# ground_station_power_board.net
KiCad netlist of a schematic drawn in EAGLE
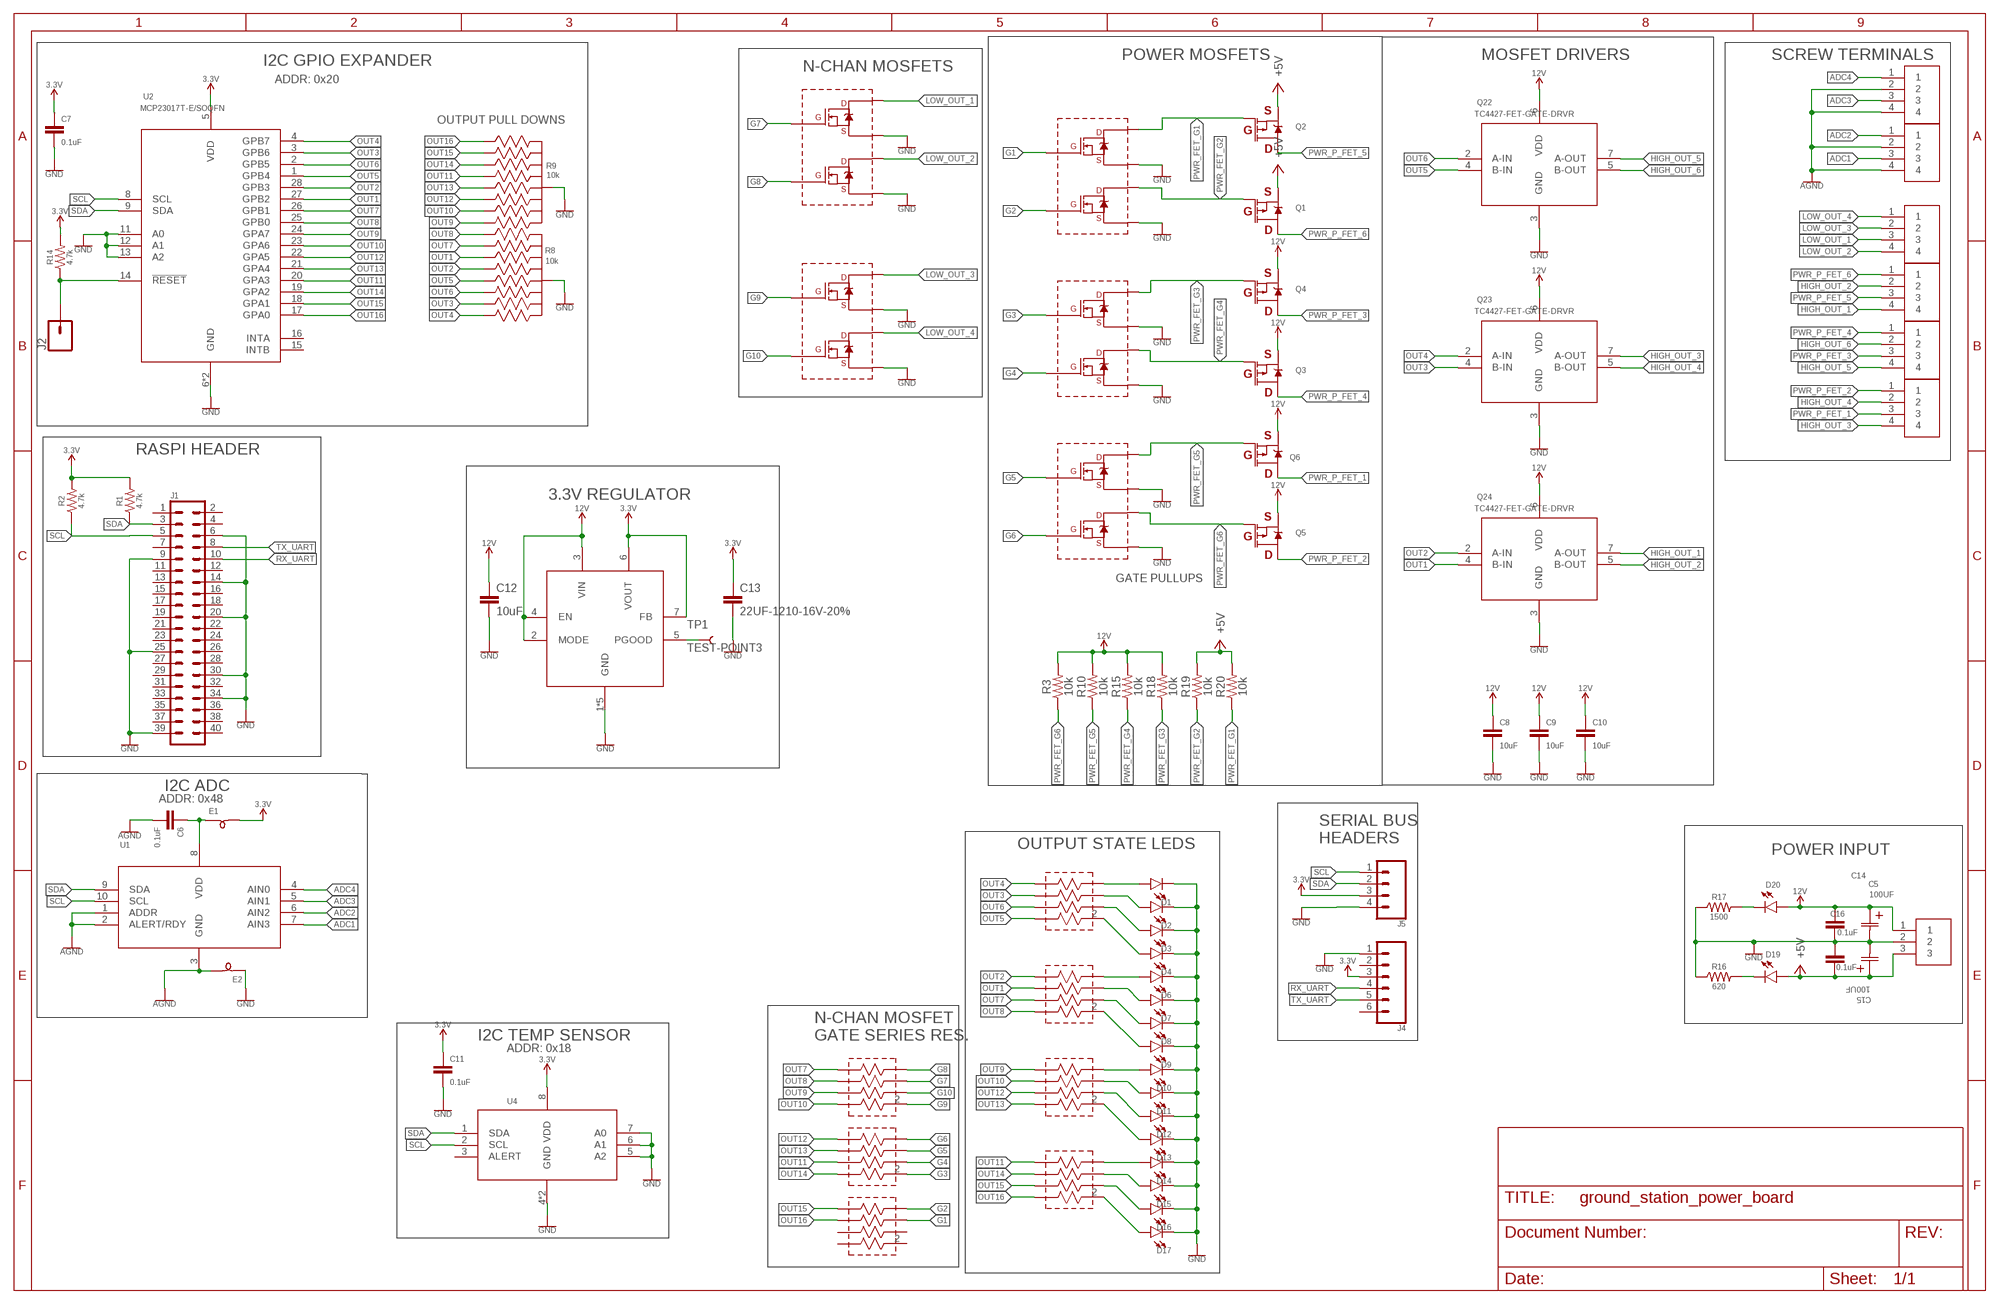
[diagram p0: schematic, sheet 1]

(export (version "E")
  (design (tool "Eeschema 10.0.6"))
  (components
    (comp (ref "C5")
      (value "100UF")
      (footprint "eagle-import:CHEMI-KE0-M")
      (fields (field (name "MANUFACTURER_PART_NUMBER") "EMVH630ARA101MKE0S"))
      (libsource (lib "eagle-import") (part "100UF-CAP-EMVH630ARA101MKE0SCHEMI-KE0-M"))
    )
    (comp (ref "C6")
      (value "0.1uF")
      (footprint "eagle-import:0603")
      (libsource (lib "eagle-import") (part "0.1UF-0603-25V-5%"))
    )
    (comp (ref "C7")
      (value "0.1uF")
      (footprint "eagle-import:0603")
      (libsource (lib "eagle-import") (part "0.1UF-0603-25V-5%"))
    )
    (comp (ref "C8")
      (value "10uF")
      (footprint "eagle-import:0805")
      (libsource (lib "eagle-import") (part "10UF-0805-10V-10%"))
    )
    (comp (ref "C9")
      (value "10uF")
      (footprint "eagle-import:0805")
      (libsource (lib "eagle-import") (part "10UF-0805-10V-10%"))
    )
    (comp (ref "C10")
      (value "10uF")
      (footprint "eagle-import:0805")
      (libsource (lib "eagle-import") (part "10UF-0805-10V-10%"))
    )
    (comp (ref "C11")
      (value "0.1uF")
      (footprint "eagle-import:0603")
      (libsource (lib "eagle-import") (part "0.1UF-0603-25V-5%"))
    )
    (comp (ref "C12")
      (value "10uF")
      (footprint "eagle-import:1206")
      (libsource (lib "eagle-import") (part "10UF-1206-6.3V-20%"))
    )
    (comp (ref "C13")
      (value "22UF-1210-16V-20%")
      (footprint "eagle-import:1210")
      (libsource (lib "eagle-import") (part "22UF-1210-16V-20%"))
    )
    (comp (ref "C14")
      (value "0.1uF")
      (footprint "eagle-import:0603")
      (libsource (lib "eagle-import") (part "0.1UF-0603-25V-5%"))
    )
    (comp (ref "C15")
      (value "100UF")
      (footprint "eagle-import:CHEMI-KE0-M")
      (fields (field (name "MANUFACTURER_PART_NUMBER") "EMVH630ARA101MKE0S"))
      (libsource (lib "eagle-import") (part "100UF-CAP-EMVH630ARA101MKE0SCHEMI-KE0-M"))
    )
    (comp (ref "C16")
      (value "0.1uF")
      (footprint "eagle-import:0603")
      (libsource (lib "eagle-import") (part "0.1UF-0603-25V-5%"))
    )
    (comp (ref "D1")
      (value "LED0603")
      (footprint "eagle-import:LED-0603")
      (libsource (lib "eagle-import") (part "LED0603"))
    )
    (comp (ref "D2")
      (value "LED0603")
      (footprint "eagle-import:LED-0603")
      (libsource (lib "eagle-import") (part "LED0603"))
    )
    (comp (ref "D3")
      (value "LED0603")
      (footprint "eagle-import:LED-0603")
      (libsource (lib "eagle-import") (part "LED0603"))
    )
    (comp (ref "D4")
      (value "LED0603")
      (footprint "eagle-import:LED-0603")
      (libsource (lib "eagle-import") (part "LED0603"))
    )
    (comp (ref "D6")
      (value "LED0603")
      (footprint "eagle-import:LED-0603")
      (libsource (lib "eagle-import") (part "LED0603"))
    )
    (comp (ref "D7")
      (value "LED0603")
      (footprint "eagle-import:LED-0603")
      (libsource (lib "eagle-import") (part "LED0603"))
    )
    (comp (ref "D8")
      (value "LED0603")
      (footprint "eagle-import:LED-0603")
      (libsource (lib "eagle-import") (part "LED0603"))
    )
    (comp (ref "D9")
      (value "LED0603")
      (footprint "eagle-import:LED-0603")
      (libsource (lib "eagle-import") (part "LED0603"))
    )
    (comp (ref "D10")
      (value "LED0603")
      (footprint "eagle-import:LED-0603")
      (libsource (lib "eagle-import") (part "LED0603"))
    )
    (comp (ref "D11")
      (value "LED0603")
      (footprint "eagle-import:LED-0603")
      (libsource (lib "eagle-import") (part "LED0603"))
    )
    (comp (ref "D12")
      (value "LED0603")
      (footprint "eagle-import:LED-0603")
      (libsource (lib "eagle-import") (part "LED0603"))
    )
    (comp (ref "D13")
      (value "LED0603")
      (footprint "eagle-import:LED-0603")
      (libsource (lib "eagle-import") (part "LED0603"))
    )
    (comp (ref "D14")
      (value "LED0603")
      (footprint "eagle-import:LED-0603")
      (libsource (lib "eagle-import") (part "LED0603"))
    )
    (comp (ref "D15")
      (value "LED0603")
      (footprint "eagle-import:LED-0603")
      (libsource (lib "eagle-import") (part "LED0603"))
    )
    (comp (ref "D16")
      (value "LED0603")
      (footprint "eagle-import:LED-0603")
      (libsource (lib "eagle-import") (part "LED0603"))
    )
    (comp (ref "D17")
      (value "LED0603")
      (footprint "eagle-import:LED-0603")
      (libsource (lib "eagle-import") (part "LED0603"))
    )
    (comp (ref "D19")
      (value "LED0603")
      (footprint "eagle-import:LED-0603")
      (libsource (lib "eagle-import") (part "LED0603"))
    )
    (comp (ref "D20")
      (value "LED0603")
      (footprint "eagle-import:LED-0603")
      (libsource (lib "eagle-import") (part "LED0603"))
    )
    (comp (ref "E1")
      (value "L-BEAD-0805-B")
      (footprint "eagle-import:.0805-B")
      (libsource (lib "eagle-import") (part "L-BEAD-0805-B"))
    )
    (comp (ref "E2")
      (value "L-BEAD-0805-B")
      (footprint "eagle-import:.0805-B")
      (libsource (lib "eagle-import") (part "L-BEAD-0805-B"))
    )
    (comp (ref "J1")
      (value "CONN_20X2SHROUDED")
      (footprint "eagle-import:2X20_SHROUDED")
      (libsource (lib "eagle-import") (part "CONN_20X2SHROUDED"))
    )
    (comp (ref "J2")
      (value "CONN_01PTH_NO_SILK_KIT")
      (footprint "eagle-import:1X01NS_KIT")
      (libsource (lib "eagle-import") (part "CONN_01PTH_NO_SILK_KIT"))
    )
    (comp (ref "J4")
      (value "CONN_06LONGPADS")
      (footprint "eagle-import:1X06_LONGPADS")
      (libsource (lib "eagle-import") (part "CONN_06LONGPADS"))
    )
    (comp (ref "J5")
      (value "CONN_04LONGPADS")
      (footprint "eagle-import:1X04_LONGPADS")
      (libsource (lib "eagle-import") (part "CONN_04LONGPADS"))
    )
    (comp (ref "Q1")
      (value "SQJ459EP_MOSFET_P_CHAN")
      (footprint "eagle-import:POWERPAK_S0-8L")
      (libsource (lib "eagle-import") (part "SQJ459EP_MOSFET_P_CHAN"))
    )
    (comp (ref "Q2")
      (value "SQJ459EP_MOSFET_P_CHAN")
      (footprint "eagle-import:POWERPAK_S0-8L")
      (libsource (lib "eagle-import") (part "SQJ459EP_MOSFET_P_CHAN"))
    )
    (comp (ref "Q3")
      (value "SQJ459EP_MOSFET_P_CHAN")
      (footprint "eagle-import:POWERPAK_S0-8L")
      (libsource (lib "eagle-import") (part "SQJ459EP_MOSFET_P_CHAN"))
    )
    (comp (ref "Q4")
      (value "SQJ459EP_MOSFET_P_CHAN")
      (footprint "eagle-import:POWERPAK_S0-8L")
      (libsource (lib "eagle-import") (part "SQJ459EP_MOSFET_P_CHAN"))
    )
    (comp (ref "Q5")
      (value "SQJ459EP_MOSFET_P_CHAN")
      (footprint "eagle-import:POWERPAK_S0-8L")
      (libsource (lib "eagle-import") (part "SQJ459EP_MOSFET_P_CHAN"))
    )
    (comp (ref "Q6")
      (value "SQJ459EP_MOSFET_P_CHAN")
      (footprint "eagle-import:POWERPAK_S0-8L")
      (libsource (lib "eagle-import") (part "SQJ459EP_MOSFET_P_CHAN"))
    )
    (comp (ref "Q8")
      (value "DMN61D8LVT-DUAL-N-CHANNEL-MOSFET")
      (footprint "eagle-import:TSOT26")
      (libsource (lib "eagle-import") (part "DMN61D8LVT-DUAL-N-CHANNEL-MOSFET"))
    )
    (comp (ref "Q9")
      (value "DMN61D8LVT-DUAL-N-CHANNEL-MOSFET")
      (footprint "eagle-import:TSOT26")
      (libsource (lib "eagle-import") (part "DMN61D8LVT-DUAL-N-CHANNEL-MOSFET"))
    )
    (comp (ref "Q15")
      (value "DMN61D8LVT-DUAL-N-CHANNEL-MOSFET")
      (footprint "eagle-import:TSOT26")
      (libsource (lib "eagle-import") (part "DMN61D8LVT-DUAL-N-CHANNEL-MOSFET"))
    )
    (comp (ref "Q17")
      (value "DMN61D8LVT-DUAL-N-CHANNEL-MOSFET")
      (footprint "eagle-import:TSOT26")
      (libsource (lib "eagle-import") (part "DMN61D8LVT-DUAL-N-CHANNEL-MOSFET"))
    )
    (comp (ref "Q18")
      (value "DMN61D8LVT-DUAL-N-CHANNEL-MOSFET")
      (footprint "eagle-import:TSOT26")
      (libsource (lib "eagle-import") (part "DMN61D8LVT-DUAL-N-CHANNEL-MOSFET"))
    )
    (comp (ref "Q22")
      (value "TC4427-FET-GATE-DRVR")
      (footprint "eagle-import:TSSOP-8")
      (libsource (lib "eagle-import") (part "TC4427-FET-GATE-DRVR"))
    )
    (comp (ref "Q23")
      (value "TC4427-FET-GATE-DRVR")
      (footprint "eagle-import:TSSOP-8")
      (libsource (lib "eagle-import") (part "TC4427-FET-GATE-DRVR"))
    )
    (comp (ref "Q24")
      (value "TC4427-FET-GATE-DRVR")
      (footprint "eagle-import:TSSOP-8")
      (libsource (lib "eagle-import") (part "TC4427-FET-GATE-DRVR"))
    )
    (comp (ref "R1")
      (value "4.7k")
      (footprint "eagle-import:0603")
      (libsource (lib "eagle-import") (part "4.7KOHM-0603-1/10W-1%"))
    )
    (comp (ref "R2")
      (value "4.7k")
      (footprint "eagle-import:0603")
      (libsource (lib "eagle-import") (part "4.7KOHM-0603-1/10W-1%"))
    )
    (comp (ref "R3")
      (value "10k")
      (footprint "eagle-import:0603")
      (libsource (lib "eagle-import") (part "10KOHM-0603-1/10W-1%"))
    )
    (comp (ref "R4")
      (value "680")
      (footprint "eagle-import:RES-ARRAY-742C083")
      (libsource (lib "eagle-import") (part "RES-ARRAY-742C083"))
    )
    (comp (ref "R5")
      (value "680")
      (footprint "eagle-import:RES-ARRAY-742C083")
      (libsource (lib "eagle-import") (part "RES-ARRAY-742C083"))
    )
    (comp (ref "R6")
      (value "680")
      (footprint "eagle-import:RES-ARRAY-742C083")
      (libsource (lib "eagle-import") (part "RES-ARRAY-742C083"))
    )
    (comp (ref "R7")
      (value "680")
      (footprint "eagle-import:RES-ARRAY-742C083")
      (libsource (lib "eagle-import") (part "RES-ARRAY-742C083"))
    )
    (comp (ref "R8")
      (value "10k")
      (footprint "eagle-import:C_ARRAY_EXBA-M")
      (fields (field (name "MANUFACTURER_PART_NUMBER") "EXBA10P391J"))
      (libsource (lib "eagle-import") (part "EXB-A10P391JC_ARRAY_EXBA-M"))
    )
    (comp (ref "R9")
      (value "10k")
      (footprint "eagle-import:C_ARRAY_EXBA-M")
      (fields (field (name "MANUFACTURER_PART_NUMBER") "EXBA10P391J"))
      (libsource (lib "eagle-import") (part "EXB-A10P391JC_ARRAY_EXBA-M"))
    )
    (comp (ref "R10")
      (value "10k")
      (footprint "eagle-import:0603")
      (libsource (lib "eagle-import") (part "10KOHM-0603-1/10W-1%"))
    )
    (comp (ref "R11")
      (value "220")
      (footprint "eagle-import:RES-ARRAY-742C083")
      (libsource (lib "eagle-import") (part "RES-ARRAY-742C083"))
    )
    (comp (ref "R12")
      (value "220")
      (footprint "eagle-import:RES-ARRAY-742C083")
      (libsource (lib "eagle-import") (part "RES-ARRAY-742C083"))
    )
    (comp (ref "R13")
      (value "220")
      (footprint "eagle-import:RES-ARRAY-742C083")
      (libsource (lib "eagle-import") (part "RES-ARRAY-742C083"))
    )
    (comp (ref "R14")
      (value "4.7k")
      (footprint "eagle-import:0603")
      (libsource (lib "eagle-import") (part "4.7KOHM-0603-1/10W-1%"))
    )
    (comp (ref "R15")
      (value "10k")
      (footprint "eagle-import:0603")
      (libsource (lib "eagle-import") (part "10KOHM-0603-1/10W-1%"))
    )
    (comp (ref "R16")
      (value "620")
      (footprint "eagle-import:0603")
      (libsource (lib "eagle-import") (part "4.7KOHM-0603-1/10W-1%"))
    )
    (comp (ref "R17")
      (value "1500")
      (footprint "eagle-import:0603")
      (libsource (lib "eagle-import") (part "4.7KOHM-0603-1/10W-1%"))
    )
    (comp (ref "R18")
      (value "10k")
      (footprint "eagle-import:0603")
      (libsource (lib "eagle-import") (part "10KOHM-0603-1/10W-1%"))
    )
    (comp (ref "R19")
      (value "10k")
      (footprint "eagle-import:0603")
      (libsource (lib "eagle-import") (part "10KOHM-0603-1/10W-1%"))
    )
    (comp (ref "R20")
      (value "10k")
      (footprint "eagle-import:0603")
      (libsource (lib "eagle-import") (part "10KOHM-0603-1/10W-1%"))
    )
    (comp (ref "TP1")
      (value "TEST-POINT3")
      (footprint "eagle-import:PAD.03X.03")
      (libsource (lib "eagle-import") (part "TEST-POINT3"))
    )
    (comp (ref "U$1")
      (value "1719031-PHONEIX-CONTACT-DBL-TERMINAL-BLOCK")
      (footprint "eagle-import:1719031-PHONEIX-CONTACT-DBL-TERMINAL-BLOCK")
      (libsource (lib "eagle-import") (part "1719031-PHONEIX-CONTACT-DBL-TERMINAL-BLOCK"))
    )
    (comp (ref "U$2")
      (value "1719031-PHONEIX-CONTACT-DBL-TERMINAL-BLOCK")
      (footprint "eagle-import:1719031-PHONEIX-CONTACT-DBL-TERMINAL-BLOCK")
      (libsource (lib "eagle-import") (part "1719031-PHONEIX-CONTACT-DBL-TERMINAL-BLOCK"))
    )
    (comp (ref "U$3")
      (value "1719031-PHONEIX-CONTACT-DBL-TERMINAL-BLOCK")
      (footprint "eagle-import:1719031-PHONEIX-CONTACT-DBL-TERMINAL-BLOCK")
      (libsource (lib "eagle-import") (part "1719031-PHONEIX-CONTACT-DBL-TERMINAL-BLOCK"))
    )
    (comp (ref "U$4")
      (value "1719031-PHONEIX-CONTACT-DBL-TERMINAL-BLOCK")
      (footprint "eagle-import:1719031-PHONEIX-CONTACT-DBL-TERMINAL-BLOCK")
      (libsource (lib "eagle-import") (part "1719031-PHONEIX-CONTACT-DBL-TERMINAL-BLOCK"))
    )
    (comp (ref "U$5")
      (value "1719031-PHONEIX-CONTACT-DBL-TERMINAL-BLOCK")
      (footprint "eagle-import:1719031-PHONEIX-CONTACT-DBL-TERMINAL-BLOCK")
      (libsource (lib "eagle-import") (part "1719031-PHONEIX-CONTACT-DBL-TERMINAL-BLOCK"))
    )
    (comp (ref "U$6")
      (value "1719031-PHONEIX-CONTACT-DBL-TERMINAL-BLOCK")
      (footprint "eagle-import:1719031-PHONEIX-CONTACT-DBL-TERMINAL-BLOCK")
      (libsource (lib "eagle-import") (part "1719031-PHONEIX-CONTACT-DBL-TERMINAL-BLOCK"))
    )
    (comp (ref "U$9")
      (value "LMZM23601V3SILT")
      (footprint "eagle-import:MICRO-SIP")
      (libsource (lib "eagle-import") (part "LMZM23601V3SILT"))
    )
    (comp (ref "U$11")
      (value "1714968-PHONEIX-CONTACT-TERMINAL-BLOCK")
      (footprint "eagle-import:1714968-PHONEIX-CONTACT-3-TERMINAL-BLOCK")
      (libsource (lib "eagle-import") (part "1714968-PHONEIX-CONTACT-TERMINAL-BLOCK"))
    )
    (comp (ref "U1")
      (value "ADS1115IDGSTDGS10-M")
      (footprint "eagle-import:DGS10-M")
      (fields (field (name "MANUFACTURER_PART_NUMBER") "ADS1115IDGST"))
      (libsource (lib "eagle-import") (part "ADS1115IDGSTDGS10-M"))
    )
    (comp (ref "U2")
      (value "MCP23017T-E/SOQFN")
      (footprint "eagle-import:QFN28_6X6MC-M")
      (libsource (lib "eagle-import") (part "MCP23017T-E/SOQFN"))
    )
    (comp (ref "U4")
      (value "MCP9808T-E/MCDFN8_2X3MC-M")
      (footprint "eagle-import:DFN8_2X3MC-M")
      (fields (field (name "MANUFACTURER_PART_NUMBER") "MCP9808TEMC"))
      (libsource (lib "eagle-import") (part "MCP9808T-E/MCDFN8_2X3MC-M"))
    )
  )
  (nets
    (net (code "1") (name "+5V") (class "Default")
      (node (ref "C15") (pin "1") (pinfunction "11_1") (pintype "passive"))
      (node (ref "C16") (pin "2") (pinfunction "2_2") (pintype "passive"))
      (node (ref "D19") (pin "A") (pinfunction "A_A") (pintype "passive"))
      (node (ref "Q1") (pin "S1") (pinfunction "S_S1") (pintype "bidirectional"))
      (node (ref "Q1") (pin "S2") (pinfunction "S_S2") (pintype "bidirectional"))
      (node (ref "Q1") (pin "S3") (pinfunction "S_S3") (pintype "bidirectional"))
      (node (ref "Q2") (pin "S1") (pinfunction "S_S1") (pintype "bidirectional"))
      (node (ref "Q2") (pin "S2") (pinfunction "S_S2") (pintype "bidirectional"))
      (node (ref "Q2") (pin "S3") (pinfunction "S_S3") (pintype "bidirectional"))
      (node (ref "R19") (pin "2") (pinfunction "2_2") (pintype "passive"))
      (node (ref "R20") (pin "2") (pinfunction "2_2") (pintype "passive"))
      (node (ref "U$11") (pin "3") (pinfunction "3_3") (pintype "bidirectional"))
    )
    (net (code "2") (name "3.3V") (class "Default")
      (node (ref "C11") (pin "1") (pinfunction "1_1") (pintype "passive"))
      (node (ref "C13") (pin "1") (pinfunction "1_1") (pintype "passive"))
      (node (ref "C7") (pin "1") (pinfunction "1_1") (pintype "passive"))
      (node (ref "E1") (pin "2") (pinfunction "2_2") (pintype "passive"))
      (node (ref "J4") (pin "3") (pinfunction "3_3") (pintype "passive"))
      (node (ref "J5") (pin "3") (pinfunction "3_3") (pintype "passive"))
      (node (ref "R1") (pin "2") (pinfunction "2_2") (pintype "passive"))
      (node (ref "R14") (pin "2") (pinfunction "2_2") (pintype "passive"))
      (node (ref "R2") (pin "2") (pinfunction "2_2") (pintype "passive"))
      (node (ref "U$9") (pin "6") (pinfunction "VOUT_6") (pintype "bidirectional"))
      (node (ref "U$9") (pin "7") (pinfunction "FB_7") (pintype "bidirectional"))
      (node (ref "U2") (pin "5") (pinfunction "VDD_5") (pintype "passive"))
      (node (ref "U4") (pin "8") (pinfunction "VDD_8") (pintype "power_in"))
    )
    (net (code "3") (name "12V") (class "Default")
      (node (ref "C10") (pin "1") (pinfunction "1_1") (pintype "passive"))
      (node (ref "C12") (pin "1") (pinfunction "1_1") (pintype "passive"))
      (node (ref "C14") (pin "1") (pinfunction "1_1") (pintype "passive"))
      (node (ref "C5") (pin "1") (pinfunction "11_1") (pintype "passive"))
      (node (ref "C8") (pin "1") (pinfunction "1_1") (pintype "passive"))
      (node (ref "C9") (pin "1") (pinfunction "1_1") (pintype "passive"))
      (node (ref "D20") (pin "A") (pinfunction "A_A") (pintype "passive"))
      (node (ref "Q22") (pin "6") (pinfunction "VDD_6") (pintype "passive"))
      (node (ref "Q23") (pin "6") (pinfunction "VDD_6") (pintype "passive"))
      (node (ref "Q24") (pin "6") (pinfunction "VDD_6") (pintype "passive"))
      (node (ref "Q3") (pin "S1") (pinfunction "S_S1") (pintype "bidirectional"))
      (node (ref "Q3") (pin "S2") (pinfunction "S_S2") (pintype "bidirectional"))
      (node (ref "Q3") (pin "S3") (pinfunction "S_S3") (pintype "bidirectional"))
      (node (ref "Q4") (pin "S1") (pinfunction "S_S1") (pintype "bidirectional"))
      (node (ref "Q4") (pin "S2") (pinfunction "S_S2") (pintype "bidirectional"))
      (node (ref "Q4") (pin "S3") (pinfunction "S_S3") (pintype "bidirectional"))
      (node (ref "Q5") (pin "S1") (pinfunction "S_S1") (pintype "bidirectional"))
      (node (ref "Q5") (pin "S2") (pinfunction "S_S2") (pintype "bidirectional"))
      (node (ref "Q5") (pin "S3") (pinfunction "S_S3") (pintype "bidirectional"))
      (node (ref "Q6") (pin "S1") (pinfunction "S_S1") (pintype "bidirectional"))
      (node (ref "Q6") (pin "S2") (pinfunction "S_S2") (pintype "bidirectional"))
      (node (ref "Q6") (pin "S3") (pinfunction "S_S3") (pintype "bidirectional"))
      (node (ref "R10") (pin "2") (pinfunction "2_2") (pintype "passive"))
      (node (ref "R15") (pin "2") (pinfunction "2_2") (pintype "passive"))
      (node (ref "R18") (pin "2") (pinfunction "2_2") (pintype "passive"))
      (node (ref "R3") (pin "2") (pinfunction "2_2") (pintype "passive"))
      (node (ref "U$11") (pin "1") (pinfunction "1_1") (pintype "bidirectional"))
      (node (ref "U$9") (pin "2") (pinfunction "MODE_2") (pintype "bidirectional"))
      (node (ref "U$9") (pin "3") (pinfunction "VIN_3") (pintype "bidirectional"))
      (node (ref "U$9") (pin "4") (pinfunction "EN_4") (pintype "bidirectional"))
    )
    (net (code "4") (name "ADC1") (class "Default")
      (node (ref "U$5") (pin "3") (pinfunction "3_3") (pintype "bidirectional"))
      (node (ref "U1") (pin "7") (pinfunction "AIN3_7") (pintype "input"))
    )
    (net (code "5") (name "ADC2") (class "Default")
      (node (ref "U$5") (pin "1") (pinfunction "1_1") (pintype "bidirectional"))
      (node (ref "U1") (pin "6") (pinfunction "AIN2_6") (pintype "input"))
    )
    (net (code "6") (name "ADC3") (class "Default")
      (node (ref "U$6") (pin "3") (pinfunction "3_3") (pintype "bidirectional"))
      (node (ref "U1") (pin "5") (pinfunction "AIN1_5") (pintype "input"))
    )
    (net (code "7") (name "ADC4") (class "Default")
      (node (ref "U$6") (pin "1") (pinfunction "1_1") (pintype "bidirectional"))
      (node (ref "U1") (pin "4") (pinfunction "AIN0_4") (pintype "input"))
    )
    (net (code "8") (name "AGND") (class "Default")
      (node (ref "C6") (pin "2") (pinfunction "2_2") (pintype "passive"))
      (node (ref "E2") (pin "2") (pinfunction "2_2") (pintype "passive"))
      (node (ref "U$5") (pin "2") (pinfunction "2_2") (pintype "bidirectional"))
      (node (ref "U$5") (pin "4") (pinfunction "4_4") (pintype "bidirectional"))
      (node (ref "U$6") (pin "2") (pinfunction "2_2") (pintype "bidirectional"))
      (node (ref "U$6") (pin "4") (pinfunction "4_4") (pintype "bidirectional"))
      (node (ref "U1") (pin "1") (pinfunction "ADDR_1") (pintype "input"))
      (node (ref "U1") (pin "2") (pinfunction "ALERT/RDY_2") (pintype "output"))
      (node (ref "U1") (pin "3") (pinfunction "GND_3") (pintype "power_in"))
    )
    (net (code "9") (name "G1") (class "Default")
      (node (ref "Q8") (pin "5") (pinfunction "G2_5") (pintype "bidirectional"))
      (node (ref "R11") (pin "6") (pinfunction "~{1OE6}_6") (pintype "bidirectional"))
    )
    (net (code "10") (name "G2") (class "Default")
      (node (ref "Q8") (pin "2") (pinfunction "G1_2") (pintype "bidirectional"))
      (node (ref "R11") (pin "8") (pinfunction "~{1OE8}_8") (pintype "bidirectional"))
    )
    (net (code "11") (name "G3") (class "Default")
      (node (ref "Q9") (pin "5") (pinfunction "G2_5") (pintype "bidirectional"))
      (node (ref "R12") (pin "2") (pinfunction "~{1OE2}_2") (pintype "bidirectional"))
    )
    (net (code "12") (name "G4") (class "Default")
      (node (ref "Q9") (pin "2") (pinfunction "G1_2") (pintype "bidirectional"))
      (node (ref "R12") (pin "4") (pinfunction "~{1OE4}_4") (pintype "bidirectional"))
    )
    (net (code "13") (name "G5") (class "Default")
      (node (ref "Q15") (pin "5") (pinfunction "G2_5") (pintype "bidirectional"))
      (node (ref "R12") (pin "6") (pinfunction "~{1OE6}_6") (pintype "bidirectional"))
    )
    (net (code "14") (name "G6") (class "Default")
      (node (ref "Q15") (pin "2") (pinfunction "G1_2") (pintype "bidirectional"))
      (node (ref "R12") (pin "8") (pinfunction "~{1OE8}_8") (pintype "bidirectional"))
    )
    (net (code "15") (name "G7") (class "Default")
      (node (ref "Q18") (pin "5") (pinfunction "G2_5") (pintype "bidirectional"))
      (node (ref "R13") (pin "6") (pinfunction "~{1OE6}_6") (pintype "bidirectional"))
    )
    (net (code "16") (name "G8") (class "Default")
      (node (ref "Q18") (pin "2") (pinfunction "G1_2") (pintype "bidirectional"))
      (node (ref "R13") (pin "8") (pinfunction "~{1OE8}_8") (pintype "bidirectional"))
    )
    (net (code "17") (name "G9") (class "Default")
      (node (ref "Q17") (pin "5") (pinfunction "G2_5") (pintype "bidirectional"))
      (node (ref "R13") (pin "2") (pinfunction "~{1OE2}_2") (pintype "bidirectional"))
    )
    (net (code "18") (name "G10") (class "Default")
      (node (ref "Q17") (pin "2") (pinfunction "G1_2") (pintype "bidirectional"))
      (node (ref "R13") (pin "4") (pinfunction "~{1OE4}_4") (pintype "bidirectional"))
    )
    (net (code "19") (name "GND") (class "Default")
      (node (ref "C10") (pin "2") (pinfunction "2_2") (pintype "passive"))
      (node (ref "C11") (pin "2") (pinfunction "2_2") (pintype "passive"))
      (node (ref "C12") (pin "2") (pinfunction "2_2") (pintype "passive"))
      (node (ref "C13") (pin "2") (pinfunction "2_2") (pintype "passive"))
      (node (ref "C14") (pin "2") (pinfunction "2_2") (pintype "passive"))
      (node (ref "C15") (pin "2") (pinfunction "22_2") (pintype "passive"))
      (node (ref "C16") (pin "1") (pinfunction "1_1") (pintype "passive"))
      (node (ref "C5") (pin "2") (pinfunction "22_2") (pintype "passive"))
      (node (ref "C7") (pin "2") (pinfunction "2_2") (pintype "passive"))
      (node (ref "C8") (pin "2") (pinfunction "2_2") (pintype "passive"))
      (node (ref "C9") (pin "2") (pinfunction "2_2") (pintype "passive"))
      (node (ref "D1") (pin "C") (pinfunction "C_C") (pintype "passive"))
      (node (ref "D10") (pin "C") (pinfunction "C_C") (pintype "passive"))
      (node (ref "D11") (pin "C") (pinfunction "C_C") (pintype "passive"))
      (node (ref "D12") (pin "C") (pinfunction "C_C") (pintype "passive"))
      (node (ref "D13") (pin "C") (pinfunction "C_C") (pintype "passive"))
      (node (ref "D14") (pin "C") (pinfunction "C_C") (pintype "passive"))
      (node (ref "D15") (pin "C") (pinfunction "C_C") (pintype "passive"))
      (node (ref "D16") (pin "C") (pinfunction "C_C") (pintype "passive"))
      (node (ref "D17") (pin "C") (pinfunction "C_C") (pintype "passive"))
      (node (ref "D2") (pin "C") (pinfunction "C_C") (pintype "passive"))
      (node (ref "D3") (pin "C") (pinfunction "C_C") (pintype "passive"))
      (node (ref "D4") (pin "C") (pinfunction "C_C") (pintype "passive"))
      (node (ref "D6") (pin "C") (pinfunction "C_C") (pintype "passive"))
      (node (ref "D7") (pin "C") (pinfunction "C_C") (pintype "passive"))
      (node (ref "D8") (pin "C") (pinfunction "C_C") (pintype "passive"))
      (node (ref "D9") (pin "C") (pinfunction "C_C") (pintype "passive"))
      (node (ref "E2") (pin "1") (pinfunction "1_1") (pintype "passive"))
      (node (ref "J1") (pin "14") (pinfunction "14_14") (pintype "passive"))
      (node (ref "J1") (pin "20") (pinfunction "20_20") (pintype "passive"))
      (node (ref "J1") (pin "25") (pinfunction "25_25") (pintype "passive"))
      (node (ref "J1") (pin "30") (pinfunction "30_30") (pintype "passive"))
      (node (ref "J1") (pin "34") (pinfunction "34_34") (pintype "passive"))
      (node (ref "J1") (pin "39") (pinfunction "39_39") (pintype "passive"))
      (node (ref "J1") (pin "6") (pinfunction "6_6") (pintype "passive"))
      (node (ref "J1") (pin "9") (pinfunction "9_9") (pintype "passive"))
      (node (ref "J4") (pin "1") (pinfunction "1_1") (pintype "passive"))
      (node (ref "J5") (pin "4") (pinfunction "4_4") (pintype "passive"))
      (node (ref "Q15") (pin "1") (pinfunction "S1_1") (pintype "bidirectional"))
      (node (ref "Q15") (pin "4") (pinfunction "S2_4") (pintype "bidirectional"))
      (node (ref "Q17") (pin "1") (pinfunction "S1_1") (pintype "bidirectional"))
      (node (ref "Q17") (pin "4") (pinfunction "S2_4") (pintype "bidirectional"))
      (node (ref "Q18") (pin "1") (pinfunction "S1_1") (pintype "bidirectional"))
      (node (ref "Q18") (pin "4") (pinfunction "S2_4") (pintype "bidirectional"))
      (node (ref "Q22") (pin "3") (pinfunction "GND_3") (pintype "passive"))
      (node (ref "Q23") (pin "3") (pinfunction "GND_3") (pintype "passive"))
      (node (ref "Q24") (pin "3") (pinfunction "GND_3") (pintype "passive"))
      (node (ref "Q8") (pin "1") (pinfunction "S1_1") (pintype "bidirectional"))
      (node (ref "Q8") (pin "4") (pinfunction "S2_4") (pintype "bidirectional"))
      (node (ref "Q9") (pin "1") (pinfunction "S1_1") (pintype "bidirectional"))
      (node (ref "Q9") (pin "4") (pinfunction "S2_4") (pintype "bidirectional"))
      (node (ref "R16") (pin "1") (pinfunction "1_1") (pintype "passive"))
      (node (ref "R17") (pin "1") (pinfunction "1_1") (pintype "passive"))
      (node (ref "R8") (pin "10") (pinfunction "55_10") (pintype "passive"))
      (node (ref "R8") (pin "5") (pinfunction "55_5") (pintype "passive"))
      (node (ref "R9") (pin "10") (pinfunction "55_10") (pintype "passive"))
      (node (ref "R9") (pin "5") (pinfunction "55_5") (pintype "passive"))
      (node (ref "U$11") (pin "2") (pinfunction "2_2") (pintype "bidirectional"))
      (node (ref "U$9") (pin "1") (pinfunction "GND_1") (pintype "bidirectional"))
      (node (ref "U$9") (pin "TP") (pinfunction "GND_TP") (pintype "bidirectional"))
      (node (ref "U$9") (pin "V1") (pinfunction "GND_V1") (pintype "bidirectional"))
      (node (ref "U$9") (pin "V2") (pinfunction "GND_V2") (pintype "bidirectional"))
      (node (ref "U$9") (pin "V3") (pinfunction "GND_V3") (pintype "bidirectional"))
      (node (ref "U2") (pin "11") (pinfunction "A0_11") (pintype "passive"))
      (node (ref "U2") (pin "12") (pinfunction "A1_12") (pintype "passive"))
      (node (ref "U2") (pin "13") (pinfunction "A2_13") (pintype "passive"))
      (node (ref "U2") (pin "29") (pinfunction "GND_29") (pintype "passive"))
      (node (ref "U2") (pin "6") (pinfunction "GND_6") (pintype "passive"))
      (node (ref "U4") (pin "4") (pinfunction "GND_4") (pintype "power_in"))
      (node (ref "U4") (pin "5") (pinfunction "A2_5") (pintype "passive"))
      (node (ref "U4") (pin "6") (pinfunction "A1_6") (pintype "passive"))
      (node (ref "U4") (pin "7") (pinfunction "A0_7") (pintype "passive"))
      (node (ref "U4") (pin "9") (pinfunction "GND_9") (pintype "power_in"))
    )
    (net (code "20") (name "HIGH_OUT_1") (class "Default")
      (node (ref "Q24") (pin "7") (pinfunction "A-OUT_7") (pintype "passive"))
      (node (ref "U$3") (pin "4") (pinfunction "4_4") (pintype "bidirectional"))
    )
    (net (code "21") (name "HIGH_OUT_2") (class "Default")
      (node (ref "Q24") (pin "5") (pinfunction "B-OUT_5") (pintype "passive"))
      (node (ref "U$3") (pin "2") (pinfunction "2_2") (pintype "bidirectional"))
    )
    (net (code "22") (name "HIGH_OUT_3") (class "Default")
      (node (ref "Q23") (pin "7") (pinfunction "A-OUT_7") (pintype "passive"))
      (node (ref "U$1") (pin "4") (pinfunction "4_4") (pintype "bidirectional"))
    )
    (net (code "23") (name "HIGH_OUT_4") (class "Default")
      (node (ref "Q23") (pin "5") (pinfunction "B-OUT_5") (pintype "passive"))
      (node (ref "U$1") (pin "2") (pinfunction "2_2") (pintype "bidirectional"))
    )
    (net (code "24") (name "HIGH_OUT_5") (class "Default")
      (node (ref "Q22") (pin "7") (pinfunction "A-OUT_7") (pintype "passive"))
      (node (ref "U$2") (pin "4") (pinfunction "4_4") (pintype "bidirectional"))
    )
    (net (code "25") (name "HIGH_OUT_6") (class "Default")
      (node (ref "Q22") (pin "5") (pinfunction "B-OUT_5") (pintype "passive"))
      (node (ref "U$2") (pin "2") (pinfunction "2_2") (pintype "bidirectional"))
    )
    (net (code "26") (name "LOW_OUT_1") (class "Default")
      (node (ref "Q18") (pin "3") (pinfunction "D2_3") (pintype "bidirectional"))
      (node (ref "U$4") (pin "3") (pinfunction "3_3") (pintype "bidirectional"))
    )
    (net (code "27") (name "LOW_OUT_2") (class "Default")
      (node (ref "Q18") (pin "6") (pinfunction "D1_6") (pintype "bidirectional"))
      (node (ref "U$4") (pin "4") (pinfunction "4_4") (pintype "bidirectional"))
    )
    (net (code "28") (name "LOW_OUT_3") (class "Default")
      (node (ref "Q17") (pin "3") (pinfunction "D2_3") (pintype "bidirectional"))
      (node (ref "U$4") (pin "2") (pinfunction "2_2") (pintype "bidirectional"))
    )
    (net (code "29") (name "LOW_OUT_4") (class "Default")
      (node (ref "Q17") (pin "6") (pinfunction "D1_6") (pintype "bidirectional"))
      (node (ref "U$4") (pin "1") (pinfunction "1_1") (pintype "bidirectional"))
    )
    (net (code "30") (name "Net-(D19-PadC)") (class "Default")
      (node (ref "D19") (pin "C") (pinfunction "C_C") (pintype "passive"))
      (node (ref "R16") (pin "2") (pinfunction "2_2") (pintype "passive"))
    )
    (net (code "31") (name "Net-(D20-PadC)") (class "Default")
      (node (ref "D20") (pin "C") (pinfunction "C_C") (pintype "passive"))
      (node (ref "R17") (pin "2") (pinfunction "2_2") (pintype "passive"))
    )
    (net (code "32") (name "Net-(R4-~{1OE2})") (class "Default")
      (node (ref "D4") (pin "A") (pinfunction "A_A") (pintype "passive"))
      (node (ref "R4") (pin "2") (pinfunction "~{1OE2}_2") (pintype "bidirectional"))
    )
    (net (code "33") (name "Net-(R4-~{1OE4})") (class "Default")
      (node (ref "D3") (pin "A") (pinfunction "A_A") (pintype "passive"))
      (node (ref "R4") (pin "4") (pinfunction "~{1OE4}_4") (pintype "bidirectional"))
    )
    (net (code "34") (name "Net-(R4-~{1OE6})") (class "Default")
      (node (ref "D2") (pin "A") (pinfunction "A_A") (pintype "passive"))
      (node (ref "R4") (pin "6") (pinfunction "~{1OE6}_6") (pintype "bidirectional"))
    )
    (net (code "35") (name "Net-(R4-~{1OE8})") (class "Default")
      (node (ref "D1") (pin "A") (pinfunction "A_A") (pintype "passive"))
      (node (ref "R4") (pin "8") (pinfunction "~{1OE8}_8") (pintype "bidirectional"))
    )
    (net (code "36") (name "Net-(R5-~{1OE2})") (class "Default")
      (node (ref "D9") (pin "A") (pinfunction "A_A") (pintype "passive"))
      (node (ref "R5") (pin "2") (pinfunction "~{1OE2}_2") (pintype "bidirectional"))
    )
    (net (code "37") (name "Net-(R5-~{1OE4})") (class "Default")
      (node (ref "D8") (pin "A") (pinfunction "A_A") (pintype "passive"))
      (node (ref "R5") (pin "4") (pinfunction "~{1OE4}_4") (pintype "bidirectional"))
    )
    (net (code "38") (name "Net-(R5-~{1OE6})") (class "Default")
      (node (ref "D7") (pin "A") (pinfunction "A_A") (pintype "passive"))
      (node (ref "R5") (pin "6") (pinfunction "~{1OE6}_6") (pintype "bidirectional"))
    )
    (net (code "39") (name "Net-(R5-~{1OE8})") (class "Default")
      (node (ref "D6") (pin "A") (pinfunction "A_A") (pintype "passive"))
      (node (ref "R5") (pin "8") (pinfunction "~{1OE8}_8") (pintype "bidirectional"))
    )
    (net (code "40") (name "Net-(R6-~{1OE2})") (class "Default")
      (node (ref "D13") (pin "A") (pinfunction "A_A") (pintype "passive"))
      (node (ref "R6") (pin "2") (pinfunction "~{1OE2}_2") (pintype "bidirectional"))
    )
    (net (code "41") (name "Net-(R6-~{1OE4})") (class "Default")
      (node (ref "D12") (pin "A") (pinfunction "A_A") (pintype "passive"))
      (node (ref "R6") (pin "4") (pinfunction "~{1OE4}_4") (pintype "bidirectional"))
    )
    (net (code "42") (name "Net-(R6-~{1OE6})") (class "Default")
      (node (ref "D11") (pin "A") (pinfunction "A_A") (pintype "passive"))
      (node (ref "R6") (pin "6") (pinfunction "~{1OE6}_6") (pintype "bidirectional"))
    )
    (net (code "43") (name "Net-(R6-~{1OE8})") (class "Default")
      (node (ref "D10") (pin "A") (pinfunction "A_A") (pintype "passive"))
      (node (ref "R6") (pin "8") (pinfunction "~{1OE8}_8") (pintype "bidirectional"))
    )
    (net (code "44") (name "Net-(R7-~{1OE2})") (class "Default")
      (node (ref "D17") (pin "A") (pinfunction "A_A") (pintype "passive"))
      (node (ref "R7") (pin "2") (pinfunction "~{1OE2}_2") (pintype "bidirectional"))
    )
    (net (code "45") (name "Net-(R7-~{1OE4})") (class "Default")
      (node (ref "D16") (pin "A") (pinfunction "A_A") (pintype "passive"))
      (node (ref "R7") (pin "4") (pinfunction "~{1OE4}_4") (pintype "bidirectional"))
    )
    (net (code "46") (name "Net-(R7-~{1OE6})") (class "Default")
      (node (ref "D15") (pin "A") (pinfunction "A_A") (pintype "passive"))
      (node (ref "R7") (pin "6") (pinfunction "~{1OE6}_6") (pintype "bidirectional"))
    )
    (net (code "47") (name "Net-(R7-~{1OE8})") (class "Default")
      (node (ref "D14") (pin "A") (pinfunction "A_A") (pintype "passive"))
      (node (ref "R7") (pin "8") (pinfunction "~{1OE8}_8") (pintype "bidirectional"))
    )
    (net (code "48") (name "Net-(TP1-1)") (class "Default")
      (node (ref "TP1") (pin "P$1") (pinfunction "1_P$1") (pintype "bidirectional"))
      (node (ref "U$9") (pin "5") (pinfunction "PGOOD_5") (pintype "bidirectional"))
    )
    (net (code "49") (name "Net-(U1-VDD)") (class "Default")
      (node (ref "C6") (pin "1") (pinfunction "1_1") (pintype "passive"))
      (node (ref "E1") (pin "1") (pinfunction "1_1") (pintype "passive"))
      (node (ref "U1") (pin "8") (pinfunction "VDD_8") (pintype "power_in"))
    )
    (net (code "50") (name "Net-(U2-~{RESET})") (class "Default")
      (node (ref "J2") (pin "1") (pinfunction "1_1") (pintype "passive"))
      (node (ref "R14") (pin "1") (pinfunction "1_1") (pintype "passive"))
      (node (ref "U2") (pin "14") (pinfunction "~{RESET}_14") (pintype "passive"))
    )
    (net (code "51") (name "OUT1") (class "Default")
      (node (ref "Q24") (pin "4") (pinfunction "B-IN_4") (pintype "passive"))
      (node (ref "R5") (pin "5") (pinfunction "~{1OE5}_5") (pintype "bidirectional"))
      (node (ref "R8") (pin "2") (pinfunction "22_2") (pintype "passive"))
      (node (ref "U2") (pin "27") (pinfunction "GPB2_27") (pintype "passive"))
    )
    (net (code "52") (name "OUT2") (class "Default")
      (node (ref "Q24") (pin "2") (pinfunction "A-IN_2") (pintype "passive"))
      (node (ref "R5") (pin "7") (pinfunction "~{1OE7}_7") (pintype "bidirectional"))
      (node (ref "R8") (pin "8") (pinfunction "88_8") (pintype "passive"))
      (node (ref "U2") (pin "28") (pinfunction "GPB3_28") (pintype "passive"))
    )
    (net (code "53") (name "OUT3") (class "Default")
      (node (ref "Q23") (pin "4") (pinfunction "B-IN_4") (pintype "passive"))
      (node (ref "R4") (pin "5") (pinfunction "~{1OE5}_5") (pintype "bidirectional"))
      (node (ref "R8") (pin "4") (pinfunction "44_4") (pintype "passive"))
      (node (ref "U2") (pin "3") (pinfunction "GPB6_3") (pintype "passive"))
    )
    (net (code "54") (name "OUT4") (class "Default")
      (node (ref "Q23") (pin "2") (pinfunction "A-IN_2") (pintype "passive"))
      (node (ref "R4") (pin "7") (pinfunction "~{1OE7}_7") (pintype "bidirectional"))
      (node (ref "R8") (pin "6") (pinfunction "66_6") (pintype "passive"))
      (node (ref "U2") (pin "4") (pinfunction "GPB7_4") (pintype "passive"))
    )
    (net (code "55") (name "OUT5") (class "Default")
      (node (ref "Q22") (pin "4") (pinfunction "B-IN_4") (pintype "passive"))
      (node (ref "R4") (pin "1") (pinfunction "~{1OE1}_1") (pintype "bidirectional"))
      (node (ref "R8") (pin "3") (pinfunction "33_3") (pintype "passive"))
      (node (ref "U2") (pin "1") (pinfunction "GPB4_1") (pintype "passive"))
    )
    (net (code "56") (name "OUT6") (class "Default")
      (node (ref "Q22") (pin "2") (pinfunction "A-IN_2") (pintype "passive"))
      (node (ref "R4") (pin "3") (pinfunction "~{1OE3}_3") (pintype "bidirectional"))
      (node (ref "R8") (pin "7") (pinfunction "77_7") (pintype "passive"))
      (node (ref "U2") (pin "2") (pinfunction "GPB5_2") (pintype "passive"))
    )
    (net (code "57") (name "OUT7") (class "Default")
      (node (ref "R13") (pin "7") (pinfunction "~{1OE7}_7") (pintype "bidirectional"))
      (node (ref "R5") (pin "3") (pinfunction "~{1OE3}_3") (pintype "bidirectional"))
      (node (ref "R8") (pin "9") (pinfunction "99_9") (pintype "passive"))
      (node (ref "U2") (pin "26") (pinfunction "GPB1_26") (pintype "passive"))
    )
    (net (code "58") (name "OUT8") (class "Default")
      (node (ref "R13") (pin "5") (pinfunction "~{1OE5}_5") (pintype "bidirectional"))
      (node (ref "R5") (pin "1") (pinfunction "~{1OE1}_1") (pintype "bidirectional"))
      (node (ref "R8") (pin "1") (pinfunction "11_1") (pintype "passive"))
      (node (ref "U2") (pin "25") (pinfunction "GPB0_25") (pintype "passive"))
    )
    (net (code "59") (name "OUT9") (class "Default")
      (node (ref "R13") (pin "3") (pinfunction "~{1OE3}_3") (pintype "bidirectional"))
      (node (ref "R6") (pin "7") (pinfunction "~{1OE7}_7") (pintype "bidirectional"))
      (node (ref "R9") (pin "6") (pinfunction "66_6") (pintype "passive"))
      (node (ref "U2") (pin "24") (pinfunction "GPA7_24") (pintype "passive"))
    )
    (net (code "60") (name "OUT10") (class "Default")
      (node (ref "R13") (pin "1") (pinfunction "~{1OE1}_1") (pintype "bidirectional"))
      (node (ref "R6") (pin "5") (pinfunction "~{1OE5}_5") (pintype "bidirectional"))
      (node (ref "R9") (pin "4") (pinfunction "44_4") (pintype "passive"))
      (node (ref "U2") (pin "23") (pinfunction "GPA6_23") (pintype "passive"))
    )
    (net (code "61") (name "OUT11") (class "Default")
      (node (ref "R12") (pin "3") (pinfunction "~{1OE3}_3") (pintype "bidirectional"))
      (node (ref "R7") (pin "7") (pinfunction "~{1OE7}_7") (pintype "bidirectional"))
      (node (ref "R9") (pin "8") (pinfunction "88_8") (pintype "passive"))
      (node (ref "U2") (pin "20") (pinfunction "GPA3_20") (pintype "passive"))
    )
    (net (code "62") (name "OUT12") (class "Default")
      (node (ref "R12") (pin "7") (pinfunction "~{1OE7}_7") (pintype "bidirectional"))
      (node (ref "R6") (pin "3") (pinfunction "~{1OE3}_3") (pintype "bidirectional"))
      (node (ref "R9") (pin "7") (pinfunction "77_7") (pintype "passive"))
      (node (ref "U2") (pin "22") (pinfunction "GPA5_22") (pintype "passive"))
    )
    (net (code "63") (name "OUT13") (class "Default")
      (node (ref "R12") (pin "5") (pinfunction "~{1OE5}_5") (pintype "bidirectional"))
      (node (ref "R6") (pin "1") (pinfunction "~{1OE1}_1") (pintype "bidirectional"))
      (node (ref "R9") (pin "3") (pinfunction "33_3") (pintype "passive"))
      (node (ref "U2") (pin "21") (pinfunction "GPA4_21") (pintype "passive"))
    )
    (net (code "64") (name "OUT14") (class "Default")
      (node (ref "R12") (pin "1") (pinfunction "~{1OE1}_1") (pintype "bidirectional"))
      (node (ref "R7") (pin "5") (pinfunction "~{1OE5}_5") (pintype "bidirectional"))
      (node (ref "R9") (pin "2") (pinfunction "22_2") (pintype "passive"))
      (node (ref "U2") (pin "19") (pinfunction "GPA2_19") (pintype "passive"))
    )
    (net (code "65") (name "OUT15") (class "Default")
      (node (ref "R11") (pin "7") (pinfunction "~{1OE7}_7") (pintype "bidirectional"))
      (node (ref "R7") (pin "3") (pinfunction "~{1OE3}_3") (pintype "bidirectional"))
      (node (ref "R9") (pin "9") (pinfunction "99_9") (pintype "passive"))
      (node (ref "U2") (pin "18") (pinfunction "GPA1_18") (pintype "passive"))
    )
    (net (code "66") (name "OUT16") (class "Default")
      (node (ref "R11") (pin "5") (pinfunction "~{1OE5}_5") (pintype "bidirectional"))
      (node (ref "R7") (pin "1") (pinfunction "~{1OE1}_1") (pintype "bidirectional"))
      (node (ref "R9") (pin "1") (pinfunction "11_1") (pintype "passive"))
      (node (ref "U2") (pin "17") (pinfunction "GPA0_17") (pintype "passive"))
    )
    (net (code "67") (name "PWR_FET_G1") (class "Default")
      (node (ref "Q2") (pin "G") (pinfunction "G_G") (pintype "bidirectional"))
      (node (ref "Q8") (pin "3") (pinfunction "D2_3") (pintype "bidirectional"))
      (node (ref "R20") (pin "1") (pinfunction "1_1") (pintype "passive"))
    )
    (net (code "68") (name "PWR_FET_G2") (class "Default")
      (node (ref "Q1") (pin "G") (pinfunction "G_G") (pintype "bidirectional"))
      (node (ref "Q8") (pin "6") (pinfunction "D1_6") (pintype "bidirectional"))
      (node (ref "R19") (pin "1") (pinfunction "1_1") (pintype "passive"))
    )
    (net (code "69") (name "PWR_FET_G3") (class "Default")
      (node (ref "Q4") (pin "G") (pinfunction "G_G") (pintype "bidirectional"))
      (node (ref "Q9") (pin "3") (pinfunction "D2_3") (pintype "bidirectional"))
      (node (ref "R18") (pin "1") (pinfunction "1_1") (pintype "passive"))
    )
    (net (code "70") (name "PWR_FET_G4") (class "Default")
      (node (ref "Q3") (pin "G") (pinfunction "G_G") (pintype "bidirectional"))
      (node (ref "Q9") (pin "6") (pinfunction "D1_6") (pintype "bidirectional"))
      (node (ref "R15") (pin "1") (pinfunction "1_1") (pintype "passive"))
    )
    (net (code "71") (name "PWR_FET_G5") (class "Default")
      (node (ref "Q15") (pin "3") (pinfunction "D2_3") (pintype "bidirectional"))
      (node (ref "Q6") (pin "G") (pinfunction "G_G") (pintype "bidirectional"))
      (node (ref "R10") (pin "1") (pinfunction "1_1") (pintype "passive"))
    )
    (net (code "72") (name "PWR_FET_G6") (class "Default")
      (node (ref "Q15") (pin "6") (pinfunction "D1_6") (pintype "bidirectional"))
      (node (ref "Q5") (pin "G") (pinfunction "G_G") (pintype "bidirectional"))
      (node (ref "R3") (pin "1") (pinfunction "1_1") (pintype "passive"))
    )
    (net (code "73") (name "PWR_P_FET_1") (class "Default")
      (node (ref "Q6") (pin "D1") (pinfunction "D_D1") (pintype "bidirectional"))
      (node (ref "U$1") (pin "3") (pinfunction "3_3") (pintype "bidirectional"))
    )
    (net (code "74") (name "PWR_P_FET_2") (class "Default")
      (node (ref "Q5") (pin "D1") (pinfunction "D_D1") (pintype "bidirectional"))
      (node (ref "U$1") (pin "1") (pinfunction "1_1") (pintype "bidirectional"))
    )
    (net (code "75") (name "PWR_P_FET_3") (class "Default")
      (node (ref "Q4") (pin "D1") (pinfunction "D_D1") (pintype "bidirectional"))
      (node (ref "U$2") (pin "3") (pinfunction "3_3") (pintype "bidirectional"))
    )
    (net (code "76") (name "PWR_P_FET_4") (class "Default")
      (node (ref "Q3") (pin "D1") (pinfunction "D_D1") (pintype "bidirectional"))
      (node (ref "U$2") (pin "1") (pinfunction "1_1") (pintype "bidirectional"))
    )
    (net (code "77") (name "PWR_P_FET_5") (class "Default")
      (node (ref "Q2") (pin "D1") (pinfunction "D_D1") (pintype "bidirectional"))
      (node (ref "U$3") (pin "3") (pinfunction "3_3") (pintype "bidirectional"))
    )
    (net (code "78") (name "PWR_P_FET_6") (class "Default")
      (node (ref "Q1") (pin "D1") (pinfunction "D_D1") (pintype "bidirectional"))
      (node (ref "U$3") (pin "1") (pinfunction "1_1") (pintype "bidirectional"))
    )
    (net (code "79") (name "RX_UART") (class "Default")
      (node (ref "J1") (pin "10") (pinfunction "10_10") (pintype "passive"))
      (node (ref "J4") (pin "4") (pinfunction "4_4") (pintype "passive"))
    )
    (net (code "80") (name "SCL") (class "Default")
      (node (ref "J1") (pin "5") (pinfunction "5_5") (pintype "passive"))
      (node (ref "J5") (pin "1") (pinfunction "1_1") (pintype "passive"))
      (node (ref "R2") (pin "1") (pinfunction "1_1") (pintype "passive"))
      (node (ref "U1") (pin "10") (pinfunction "SCL_10") (pintype "input"))
      (node (ref "U2") (pin "8") (pinfunction "SCL_8") (pintype "passive"))
      (node (ref "U4") (pin "2") (pinfunction "SCL_2") (pintype "passive"))
    )
    (net (code "81") (name "SDA") (class "Default")
      (node (ref "J1") (pin "3") (pinfunction "3_3") (pintype "passive"))
      (node (ref "J5") (pin "2") (pinfunction "2_2") (pintype "passive"))
      (node (ref "R1") (pin "1") (pinfunction "1_1") (pintype "passive"))
      (node (ref "U1") (pin "9") (pinfunction "SDA_9") (pintype "bidirectional"))
      (node (ref "U2") (pin "9") (pinfunction "SDA_9") (pintype "passive"))
      (node (ref "U4") (pin "1") (pinfunction "SDA_1") (pintype "passive"))
    )
    (net (code "82") (name "TX_UART") (class "Default")
      (node (ref "J1") (pin "8") (pinfunction "8_8") (pintype "passive"))
      (node (ref "J4") (pin "5") (pinfunction "5_5") (pintype "passive"))
    )
    (net (code "83") (name "unconnected-(J1-Pad1)") (class "Default")
      (node (ref "J1") (pin "1") (pinfunction "1_1") (pintype "passive"))
    )
    (net (code "84") (name "unconnected-(J1-Pad2)") (class "Default")
      (node (ref "J1") (pin "2") (pinfunction "2_2") (pintype "passive"))
    )
    (net (code "85") (name "unconnected-(J1-Pad4)") (class "Default")
      (node (ref "J1") (pin "4") (pinfunction "4_4") (pintype "passive"))
    )
    (net (code "86") (name "unconnected-(J1-Pad7)") (class "Default")
      (node (ref "J1") (pin "7") (pinfunction "7_7") (pintype "passive"))
    )
    (net (code "87") (name "unconnected-(J1-Pad11)") (class "Default")
      (node (ref "J1") (pin "11") (pinfunction "11_11") (pintype "passive"))
    )
    (net (code "88") (name "unconnected-(J1-Pad12)") (class "Default")
      (node (ref "J1") (pin "12") (pinfunction "12_12") (pintype "passive"))
    )
    (net (code "89") (name "unconnected-(J1-Pad13)") (class "Default")
      (node (ref "J1") (pin "13") (pinfunction "13_13") (pintype "passive"))
    )
    (net (code "90") (name "unconnected-(J1-Pad15)") (class "Default")
      (node (ref "J1") (pin "15") (pinfunction "15_15") (pintype "passive"))
    )
    (net (code "91") (name "unconnected-(J1-Pad16)") (class "Default")
      (node (ref "J1") (pin "16") (pinfunction "16_16") (pintype "passive"))
    )
    (net (code "92") (name "unconnected-(J1-Pad17)") (class "Default")
      (node (ref "J1") (pin "17") (pinfunction "17_17") (pintype "passive"))
    )
    (net (code "93") (name "unconnected-(J1-Pad18)") (class "Default")
      (node (ref "J1") (pin "18") (pinfunction "18_18") (pintype "passive"))
    )
    (net (code "94") (name "unconnected-(J1-Pad19)") (class "Default")
      (node (ref "J1") (pin "19") (pinfunction "19_19") (pintype "passive"))
    )
    (net (code "95") (name "unconnected-(J1-Pad21)") (class "Default")
      (node (ref "J1") (pin "21") (pinfunction "21_21") (pintype "passive"))
    )
    (net (code "96") (name "unconnected-(J1-Pad22)") (class "Default")
      (node (ref "J1") (pin "22") (pinfunction "22_22") (pintype "passive"))
    )
    (net (code "97") (name "unconnected-(J1-Pad23)") (class "Default")
      (node (ref "J1") (pin "23") (pinfunction "23_23") (pintype "passive"))
    )
    (net (code "98") (name "unconnected-(J1-Pad24)") (class "Default")
      (node (ref "J1") (pin "24") (pinfunction "24_24") (pintype "passive"))
    )
    (net (code "99") (name "unconnected-(J1-Pad26)") (class "Default")
      (node (ref "J1") (pin "26") (pinfunction "26_26") (pintype "passive"))
    )
    (net (code "100") (name "unconnected-(J1-Pad27)") (class "Default")
      (node (ref "J1") (pin "27") (pinfunction "27_27") (pintype "passive"))
    )
    (net (code "101") (name "unconnected-(J1-Pad28)") (class "Default")
      (node (ref "J1") (pin "28") (pinfunction "28_28") (pintype "passive"))
    )
    (net (code "102") (name "unconnected-(J1-Pad29)") (class "Default")
      (node (ref "J1") (pin "29") (pinfunction "29_29") (pintype "passive"))
    )
    (net (code "103") (name "unconnected-(J1-Pad31)") (class "Default")
      (node (ref "J1") (pin "31") (pinfunction "31_31") (pintype "passive"))
    )
    (net (code "104") (name "unconnected-(J1-Pad32)") (class "Default")
      (node (ref "J1") (pin "32") (pinfunction "32_32") (pintype "passive"))
    )
    (net (code "105") (name "unconnected-(J1-Pad33)") (class "Default")
      (node (ref "J1") (pin "33") (pinfunction "33_33") (pintype "passive"))
    )
    (net (code "106") (name "unconnected-(J1-Pad35)") (class "Default")
      (node (ref "J1") (pin "35") (pinfunction "35_35") (pintype "passive"))
    )
    (net (code "107") (name "unconnected-(J1-Pad36)") (class "Default")
      (node (ref "J1") (pin "36") (pinfunction "36_36") (pintype "passive"))
    )
    (net (code "108") (name "unconnected-(J1-Pad37)") (class "Default")
      (node (ref "J1") (pin "37") (pinfunction "37_37") (pintype "passive"))
    )
    (net (code "109") (name "unconnected-(J1-Pad38)") (class "Default")
      (node (ref "J1") (pin "38") (pinfunction "38_38") (pintype "passive"))
    )
    (net (code "110") (name "unconnected-(J1-Pad40)") (class "Default")
      (node (ref "J1") (pin "40") (pinfunction "40_40") (pintype "passive"))
    )
    (net (code "111") (name "unconnected-(J4-Pad2)") (class "Default")
      (node (ref "J4") (pin "2") (pinfunction "2_2") (pintype "passive"))
    )
    (net (code "112") (name "unconnected-(J4-Pad6)") (class "Default")
      (node (ref "J4") (pin "6") (pinfunction "6_6") (pintype "passive"))
    )
    (net (code "113") (name "unconnected-(R11-~{1OE1}-Pad1)") (class "Default")
      (node (ref "R11") (pin "1") (pinfunction "~{1OE1}_1") (pintype "bidirectional"))
    )
    (net (code "114") (name "unconnected-(R11-~{1OE2}-Pad2)") (class "Default")
      (node (ref "R11") (pin "2") (pinfunction "~{1OE2}_2") (pintype "bidirectional"))
    )
    (net (code "115") (name "unconnected-(R11-~{1OE3}-Pad3)") (class "Default")
      (node (ref "R11") (pin "3") (pinfunction "~{1OE3}_3") (pintype "bidirectional"))
    )
    (net (code "116") (name "unconnected-(R11-~{1OE4}-Pad4)") (class "Default")
      (node (ref "R11") (pin "4") (pinfunction "~{1OE4}_4") (pintype "bidirectional"))
    )
    (net (code "117") (name "unconnected-(U2-INTA-Pad16)") (class "Default")
      (node (ref "U2") (pin "16") (pinfunction "INTA_16") (pintype "passive"))
    )
    (net (code "118") (name "unconnected-(U2-INTB-Pad15)") (class "Default")
      (node (ref "U2") (pin "15") (pinfunction "INTB_15") (pintype "passive"))
    )
    (net (code "119") (name "unconnected-(U4-ALERT-Pad3)") (class "Default")
      (node (ref "U4") (pin "3") (pinfunction "ALERT_3") (pintype "output"))
    )
  )
)
